# PowerAmplifier_Control.net
KiCad netlist of a schematic drawn in Altium Designer
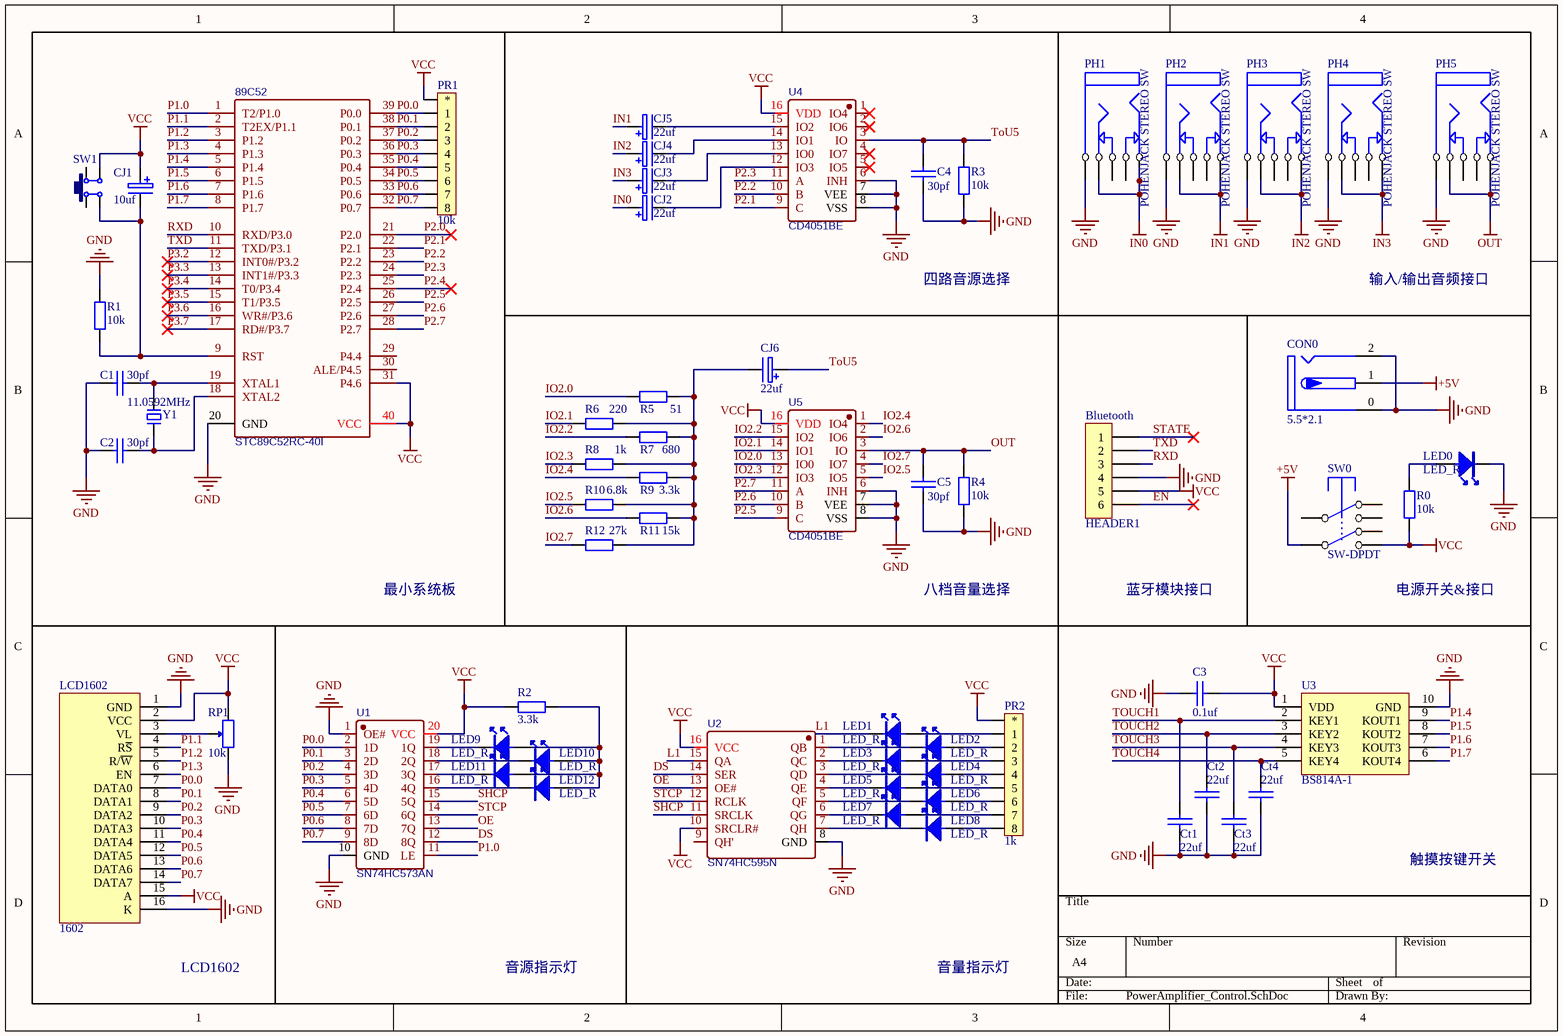
[diagram p0: PowerAmplifier_Control.SchDoc]

(export (version "E")
  (design (tool "Eeschema 10.0.6"))
  (components
    (comp (ref "89C52")
      (value "STC89C52RC-40I")
      (footprint "DIP-40_LS15.24-L52.58-W13.97-PITCH2.54")
      (fields (field (name "BOM_SUPPLIER PART") "C14022"))
      (libsource (lib "电子时钟元件库") (part "STC89C52RC-40I"))
    )
    (comp (ref "Bluetooth")
      (value "HEADER1")
      (footprint "sip-6")
      (description "Connector")
      (libsource (lib "基地库3.0mini") (part "CON6"))
    )
    (comp (ref "C1") (value "30pf") (footprint "CAP2") (libsource (lib "基地库3.0mini") (part "CAP1")))
    (comp (ref "C2") (value "30pf") (footprint "CAP2") (libsource (lib "基地库3.0mini") (part "CAP1")))
    (comp (ref "C3") (value "0.1uf") (footprint "CAP2") (libsource (lib "基地库3.0mini") (part "CAP1")))
    (comp (ref "C4") (value "30pf") (footprint "CAP2") (libsource (lib "基地库3.0mini") (part "CAP1")))
    (comp (ref "C5") (value "30pf") (footprint "CAP2") (libsource (lib "基地库3.0mini") (part "CAP1")))
    (comp (ref "CJ1") (value "10uf") (footprint "CAO1") (libsource (lib "基地库3.0mini") (part "CAP3")))
    (comp (ref "CJ2") (value "22uf") (footprint "CAO1") (libsource (lib "基地库3.0mini") (part "CAP3")))
    (comp (ref "CJ3") (value "22uf") (footprint "CAO1") (libsource (lib "基地库3.0mini") (part "CAP3")))
    (comp (ref "CJ4") (value "22uf") (footprint "CAO1") (libsource (lib "基地库3.0mini") (part "CAP3")))
    (comp (ref "CJ5") (value "22uf") (footprint "CAO1") (libsource (lib "基地库3.0mini") (part "CAP3")))
    (comp (ref "CJ6") (value "22uf") (footprint "CAO1") (libsource (lib "基地库3.0mini") (part "CAP3")))
    (comp (ref "CON0")
      (value "5.5*2.1")
      (footprint "DC-005P")
      (description "带屏蔽DC电源接口")
      (fields (field (name "版权归属") "源创客"))
      (libsource (lib "7-电源接口") (part "DC-005P"))
    )
    (comp (ref "Ct1") (value "22uf") (footprint "CAP2") (libsource (lib "基地库3.0mini") (part "CAP1")))
    (comp (ref "Ct2") (value "22uf") (footprint "CAP2") (libsource (lib "基地库3.0mini") (part "CAP1")))
    (comp (ref "Ct3") (value "22uf") (footprint "CAP2") (libsource (lib "基地库3.0mini") (part "CAP1")))
    (comp (ref "Ct4") (value "22uf") (footprint "CAP2") (libsource (lib "基地库3.0mini") (part "CAP1")))
    (comp (ref "LCD1602") (value "1602") (footprint "1602") (libsource (lib "基地库3.0mini") (part "1602")))
    (comp (ref "LED0") (value "LED_R") (footprint "LED_1206") (libsource (lib "基地库3.0mini") (part "LED")))
    (comp (ref "LED1") (value "LED_R") (footprint "LED_1206") (libsource (lib "基地库3.0mini") (part "LED")))
    (comp (ref "LED2") (value "LED_R") (footprint "LED_1206") (libsource (lib "基地库3.0mini") (part "LED")))
    (comp (ref "LED3") (value "LED_R") (footprint "LED_1206") (libsource (lib "基地库3.0mini") (part "LED")))
    (comp (ref "LED4") (value "LED_R") (footprint "LED_1206") (libsource (lib "基地库3.0mini") (part "LED")))
    (comp (ref "LED5") (value "LED_R") (footprint "LED_1206") (libsource (lib "基地库3.0mini") (part "LED")))
    (comp (ref "LED6") (value "LED_R") (footprint "LED_1206") (libsource (lib "基地库3.0mini") (part "LED")))
    (comp (ref "LED7") (value "LED_R") (footprint "LED_1206") (libsource (lib "基地库3.0mini") (part "LED")))
    (comp (ref "LED8") (value "LED_R") (footprint "LED_1206") (libsource (lib "基地库3.0mini") (part "LED")))
    (comp (ref "LED9") (value "LED_R") (footprint "LED_1206") (libsource (lib "基地库3.0mini") (part "LED")))
    (comp (ref "LED10") (value "LED_R") (footprint "LED_1206") (libsource (lib "基地库3.0mini") (part "LED")))
    (comp (ref "LED11") (value "LED_R") (footprint "LED_1206") (libsource (lib "基地库3.0mini") (part "LED")))
    (comp (ref "LED12") (value "LED_R") (footprint "LED_1206") (libsource (lib "基地库3.0mini") (part "LED")))
    (comp (ref "PH1")
      (value "POHENJACK STEREO SW")
      (footprint "POHENJACK STEREO SW")
      (libsource (lib "电子电路集成库") (part "POHENJACK STEREO SW"))
    )
    (comp (ref "PH2")
      (value "POHENJACK STEREO SW")
      (footprint "POHENJACK STEREO SW")
      (libsource (lib "电子电路集成库") (part "POHENJACK STEREO SW"))
    )
    (comp (ref "PH3")
      (value "POHENJACK STEREO SW")
      (footprint "POHENJACK STEREO SW")
      (libsource (lib "电子电路集成库") (part "POHENJACK STEREO SW"))
    )
    (comp (ref "PH4")
      (value "POHENJACK STEREO SW")
      (footprint "POHENJACK STEREO SW")
      (libsource (lib "电子电路集成库") (part "POHENJACK STEREO SW"))
    )
    (comp (ref "PH5")
      (value "POHENJACK STEREO SW")
      (footprint "POHENJACK STEREO SW")
      (libsource (lib "电子电路集成库") (part "POHENJACK STEREO SW"))
    )
    (comp (ref "PR1") (value "10k") (footprint "RP1") (libsource (lib "基地库3.0mini") (part "PRES1")))
    (comp (ref "PR2") (value "1k") (footprint "RP1") (libsource (lib "基地库3.0mini") (part "PRES1")))
    (comp (ref "R0")
      (value "10k")
      (footprint "AXIAL0.4")
      (description "贴片电阻")
      (fields (field (name "版权归属") "源创客"))
      (libsource (lib "9-电阻-电容-电感") (part "R"))
    )
    (comp (ref "R1")
      (value "10k")
      (footprint "AXIAL0.4")
      (description "贴片电阻")
      (fields (field (name "版权归属") "源创客"))
      (libsource (lib "9-电阻-电容-电感") (part "R"))
    )
    (comp (ref "R2")
      (value "3.3k")
      (footprint "AXIAL0.4")
      (description "贴片电阻")
      (fields (field (name "版权归属") "源创客"))
      (libsource (lib "9-电阻-电容-电感") (part "R"))
    )
    (comp (ref "R3")
      (value "10k")
      (footprint "AXIAL0.4")
      (description "贴片电阻")
      (fields (field (name "版权归属") "源创客"))
      (libsource (lib "9-电阻-电容-电感") (part "R"))
    )
    (comp (ref "R4")
      (value "10k")
      (footprint "AXIAL0.4")
      (description "贴片电阻")
      (fields (field (name "版权归属") "源创客"))
      (libsource (lib "9-电阻-电容-电感") (part "R"))
    )
    (comp (ref "R5")
      (value "51")
      (footprint "AXIAL0.4")
      (description "贴片电阻")
      (fields (field (name "版权归属") "源创客"))
      (libsource (lib "9-电阻-电容-电感") (part "R"))
    )
    (comp (ref "R6")
      (value "220")
      (footprint "AXIAL0.4")
      (description "贴片电阻")
      (fields (field (name "版权归属") "源创客"))
      (libsource (lib "9-电阻-电容-电感") (part "R"))
    )
    (comp (ref "R7")
      (value "680")
      (footprint "AXIAL0.4")
      (description "贴片电阻")
      (fields (field (name "版权归属") "源创客"))
      (libsource (lib "9-电阻-电容-电感") (part "R"))
    )
    (comp (ref "R8")
      (value "1k")
      (footprint "AXIAL0.4")
      (description "贴片电阻")
      (fields (field (name "版权归属") "源创客"))
      (libsource (lib "9-电阻-电容-电感") (part "R"))
    )
    (comp (ref "R9")
      (value "3.3k")
      (footprint "AXIAL0.4")
      (description "贴片电阻")
      (fields (field (name "版权归属") "源创客"))
      (libsource (lib "9-电阻-电容-电感") (part "R"))
    )
    (comp (ref "R10")
      (value "6.8k")
      (footprint "AXIAL0.4")
      (description "贴片电阻")
      (fields (field (name "版权归属") "源创客"))
      (libsource (lib "9-电阻-电容-电感") (part "R"))
    )
    (comp (ref "R11")
      (value "15k")
      (footprint "AXIAL0.4")
      (description "贴片电阻")
      (fields (field (name "版权归属") "源创客"))
      (libsource (lib "9-电阻-电容-电感") (part "R"))
    )
    (comp (ref "R12")
      (value "27k")
      (footprint "AXIAL0.4")
      (description "贴片电阻")
      (fields (field (name "版权归属") "源创客"))
      (libsource (lib "9-电阻-电容-电感") (part "R"))
    )
    (comp (ref "RP1")
      (value "10k")
      (footprint "3296W")
      (description "插件单联电位器")
      (fields (field (name "版权归属") "源创客"))
      (libsource (lib "9-电阻-电容-电感") (part "RP-ID"))
    )
    (comp (ref "SW0") (value "SW-DPDT") (footprint "SWH7*7") (libsource (lib "基地库3.0mini") (part "SW-DPDT")))
    (comp (ref "SW1")
      (value "6x6x5")
      (footprint "TSW DIP-6*6*6")
      (description "直插6x6轻触开关")
      (fields (field (name "版权归属") "源创客"))
      (libsource (lib "5-按键-开关") (part "TSW DIP-6x6"))
    )
    (comp (ref "U1")
      (value "SN74HC573AN")
      (footprint "DIP-20_L26.8-W6.4-P2.54-LS7.6-BL")
      (fields (field (name "BOM_SUPPLIER PART") "C5196"))
      (libsource (lib "74HC573AN") (part "SN74HC573AN"))
    )
    (comp (ref "U2")
      (value "SN74HC595N")
      (footprint "DIP-16_L19.8-W6.5-P2.54-LS7.6-BL")
      (fields (field (name "BOM_SUPPLIER PART") "C78711"))
      (libsource (lib "74HC595N") (part "SN74HC595N"))
    )
    (comp (ref "U3")
      (value "BS814A-1")
      (footprint "MSOP10_N")
      (description "4键电容触摸按键芯片")
      (fields (field (name "版权归属") "源创客"))
      (libsource (lib "14-IC芯片") (part "BS814A"))
    )
    (comp (ref "U4")
      (value "CD4051BE")
      (footprint "DIP-16_L20.0-W6.4-P2.54-LS7.6-BL")
      (fields (field (name "BOM_SUPPLIER PART") "C5200"))
      (libsource (lib "CD4051BE") (part "CD4051BE"))
    )
    (comp (ref "U5")
      (value "CD4051BE")
      (footprint "DIP-16_L20.0-W6.4-P2.54-LS7.6-BL")
      (fields (field (name "BOM_SUPPLIER PART") "C5200"))
      (libsource (lib "CD4051BE") (part "CD4051BE"))
    )
    (comp (ref "Y1")
      (value "11.0592MHz")
      (footprint "OSC HC-49S")
      (description "2脚无源脚晶振")
      (fields (field (name "版权归属") "源创客"))
      (libsource (lib "6-保险丝-晶振") (part "XTAL-2P"))
    )
  )
  (nets
    (net (code "1") (name "+5V") (class "Default")
      (node (ref "CON0") (pin "1") (pintype "power_in"))
      (node (ref "SW0") (pin "5") (pinfunction "5_5") (pintype "passive"))
    )
    (net (code "2") (name "/DS") (class "Default")
      (node (ref "U1") (pin "12") (pinfunction "8Q_12") (pintype "passive"))
      (node (ref "U2") (pin "14") (pinfunction "SER_14") (pintype "passive"))
    )
    (net (code "3") (name "/EN") (class "Default")
      (node (ref "Bluetooth") (pin "6") (pinfunction "6_6") (pintype "passive+no_connect"))
    )
    (net (code "4") (name "/IO2.0") (class "Default")
      (node (ref "R5") (pin "1") (pinfunction "1_1") (pintype "passive"))
      (node (ref "U5") (pin "13") (pinfunction "IO0_13") (pintype "passive"))
    )
    (net (code "5") (name "/IO2.1") (class "Default")
      (node (ref "R6") (pin "1") (pinfunction "1_1") (pintype "passive"))
      (node (ref "U5") (pin "14") (pinfunction "IO1_14") (pintype "passive"))
    )
    (net (code "6") (name "/IO2.2") (class "Default")
      (node (ref "R7") (pin "1") (pinfunction "1_1") (pintype "passive"))
      (node (ref "U5") (pin "15") (pinfunction "IO2_15") (pintype "passive"))
    )
    (net (code "7") (name "/IO2.3") (class "Default")
      (node (ref "R8") (pin "1") (pinfunction "1_1") (pintype "passive"))
      (node (ref "U5") (pin "12") (pinfunction "IO3_12") (pintype "passive"))
    )
    (net (code "8") (name "/IO2.4") (class "Default")
      (node (ref "R9") (pin "1") (pinfunction "1_1") (pintype "passive"))
      (node (ref "U5") (pin "1") (pinfunction "IO4_1") (pintype "passive"))
    )
    (net (code "9") (name "/IO2.5") (class "Default")
      (node (ref "R10") (pin "1") (pinfunction "1_1") (pintype "passive"))
      (node (ref "U5") (pin "5") (pinfunction "IO5_5") (pintype "passive"))
    )
    (net (code "10") (name "/IO2.6") (class "Default")
      (node (ref "R11") (pin "1") (pinfunction "1_1") (pintype "passive"))
      (node (ref "U5") (pin "2") (pinfunction "IO6_2") (pintype "passive"))
    )
    (net (code "11") (name "/IO2.7") (class "Default")
      (node (ref "R12") (pin "1") (pinfunction "1_1") (pintype "passive"))
      (node (ref "U5") (pin "4") (pinfunction "IO7_4") (pintype "passive"))
    )
    (net (code "12") (name "/L1") (class "Default")
      (node (ref "LED1") (pin "2") (pinfunction "2_2") (pintype "passive"))
      (node (ref "U2") (pin "15") (pinfunction "QA_15") (pintype "passive"))
    )
    (net (code "13") (name "/OE") (class "Default")
      (node (ref "U1") (pin "13") (pinfunction "7Q_13") (pintype "passive"))
      (node (ref "U2") (pin "13") (pinfunction "OE#_13") (pintype "passive"))
    )
    (net (code "14") (name "/P0.0") (class "Default")
      (node (ref "89C52") (pin "39") (pinfunction "P0.0_39") (pintype "passive"))
      (node (ref "LCD1602") (pin "7") (pinfunction "DATA0_7") (pintype "passive"))
      (node (ref "PR1") (pin "2") (pinfunction "1_2") (pintype "passive"))
      (node (ref "U1") (pin "2") (pinfunction "1D_2") (pintype "passive"))
    )
    (net (code "15") (name "/P0.1") (class "Default")
      (node (ref "89C52") (pin "38") (pinfunction "P0.1_38") (pintype "passive"))
      (node (ref "LCD1602") (pin "8") (pinfunction "DATA1_8") (pintype "passive"))
      (node (ref "PR1") (pin "3") (pinfunction "2_3") (pintype "passive"))
      (node (ref "U1") (pin "3") (pinfunction "2D_3") (pintype "passive"))
    )
    (net (code "16") (name "/P0.2") (class "Default")
      (node (ref "89C52") (pin "37") (pinfunction "P0.2_37") (pintype "passive"))
      (node (ref "LCD1602") (pin "9") (pinfunction "DATA2_9") (pintype "passive"))
      (node (ref "PR1") (pin "4") (pinfunction "3_4") (pintype "passive"))
      (node (ref "U1") (pin "4") (pinfunction "3D_4") (pintype "passive"))
    )
    (net (code "17") (name "/P0.3") (class "Default")
      (node (ref "89C52") (pin "36") (pinfunction "P0.3_36") (pintype "passive"))
      (node (ref "LCD1602") (pin "10") (pinfunction "DATA3_10") (pintype "passive"))
      (node (ref "PR1") (pin "5") (pinfunction "4_5") (pintype "passive"))
      (node (ref "U1") (pin "5") (pinfunction "4D_5") (pintype "passive"))
    )
    (net (code "18") (name "/P0.4") (class "Default")
      (node (ref "89C52") (pin "35") (pinfunction "P0.4_35") (pintype "passive"))
      (node (ref "LCD1602") (pin "11") (pinfunction "DATA4_11") (pintype "passive"))
      (node (ref "PR1") (pin "6") (pinfunction "5_6") (pintype "passive"))
      (node (ref "U1") (pin "6") (pinfunction "5D_6") (pintype "passive"))
    )
    (net (code "19") (name "/P0.5") (class "Default")
      (node (ref "89C52") (pin "34") (pinfunction "P0.5_34") (pintype "passive"))
      (node (ref "LCD1602") (pin "12") (pinfunction "DATA5_12") (pintype "passive"))
      (node (ref "PR1") (pin "7") (pinfunction "6_7") (pintype "passive"))
      (node (ref "U1") (pin "7") (pinfunction "6D_7") (pintype "passive"))
    )
    (net (code "20") (name "/P0.6") (class "Default")
      (node (ref "89C52") (pin "33") (pinfunction "P0.6_33") (pintype "passive"))
      (node (ref "LCD1602") (pin "13") (pinfunction "DATA6_13") (pintype "passive"))
      (node (ref "PR1") (pin "8") (pinfunction "7_8") (pintype "passive"))
      (node (ref "U1") (pin "8") (pinfunction "7D_8") (pintype "passive"))
    )
    (net (code "21") (name "/P0.7") (class "Default")
      (node (ref "89C52") (pin "32") (pinfunction "P0.7_32") (pintype "passive"))
      (node (ref "LCD1602") (pin "14") (pinfunction "DATA7_14") (pintype "passive"))
      (node (ref "PR1") (pin "9") (pinfunction "8_9") (pintype "passive"))
      (node (ref "U1") (pin "9") (pinfunction "8D_9") (pintype "passive"))
    )
    (net (code "22") (name "/P1.0") (class "Default")
      (node (ref "89C52") (pin "1") (pinfunction "T2/P1.0_1") (pintype "passive"))
      (node (ref "U1") (pin "11") (pinfunction "LE_11") (pintype "passive"))
    )
    (net (code "23") (name "/P1.1") (class "Default")
      (node (ref "89C52") (pin "2") (pinfunction "T2EX/P1.1_2") (pintype "passive"))
      (node (ref "LCD1602") (pin "4") (pinfunction "R~{S}_4") (pintype "passive"))
    )
    (net (code "24") (name "/P1.2") (class "Default")
      (node (ref "89C52") (pin "3") (pinfunction "P1.2_3") (pintype "passive"))
      (node (ref "LCD1602") (pin "5") (pinfunction "R/~{W}_5") (pintype "passive"))
    )
    (net (code "25") (name "/P1.3") (class "Default")
      (node (ref "89C52") (pin "4") (pinfunction "P1.3_4") (pintype "passive"))
      (node (ref "LCD1602") (pin "6") (pinfunction "EN_6") (pintype "passive"))
    )
    (net (code "26") (name "/P1.4") (class "Default")
      (node (ref "89C52") (pin "5") (pinfunction "P1.4_5") (pintype "passive"))
      (node (ref "U3") (pin "9") (pinfunction "KOUT1_9") (pintype "passive"))
    )
    (net (code "27") (name "/P1.5") (class "Default")
      (node (ref "89C52") (pin "6") (pinfunction "P1.5_6") (pintype "passive"))
      (node (ref "U3") (pin "8") (pinfunction "KOUT2_8") (pintype "passive"))
    )
    (net (code "28") (name "/P1.6") (class "Default")
      (node (ref "89C52") (pin "7") (pinfunction "P1.6_7") (pintype "passive"))
      (node (ref "U3") (pin "7") (pinfunction "KOUT3_7") (pintype "passive"))
    )
    (net (code "29") (name "/P1.7") (class "Default")
      (node (ref "89C52") (pin "8") (pinfunction "P1.7_8") (pintype "passive"))
      (node (ref "U3") (pin "6") (pinfunction "KOUT4_6") (pintype "passive"))
    )
    (net (code "30") (name "/P2.0") (class "Default")
      (node (ref "89C52") (pin "21") (pinfunction "P2.0_21") (pintype "passive+no_connect"))
    )
    (net (code "31") (name "/P2.1") (class "Default")
      (node (ref "89C52") (pin "22") (pinfunction "P2.1_22") (pintype "passive"))
      (node (ref "U4") (pin "9") (pinfunction "C_9") (pintype "passive"))
    )
    (net (code "32") (name "/P2.2") (class "Default")
      (node (ref "89C52") (pin "23") (pinfunction "P2.2_23") (pintype "passive"))
      (node (ref "U4") (pin "10") (pinfunction "B_10") (pintype "passive"))
    )
    (net (code "33") (name "/P2.3") (class "Default")
      (node (ref "89C52") (pin "24") (pinfunction "P2.3_24") (pintype "passive"))
      (node (ref "U4") (pin "11") (pinfunction "A_11") (pintype "passive"))
    )
    (net (code "34") (name "/P2.4") (class "Default")
      (node (ref "89C52") (pin "25") (pinfunction "P2.4_25") (pintype "passive+no_connect"))
    )
    (net (code "35") (name "/P2.5") (class "Default")
      (node (ref "89C52") (pin "26") (pinfunction "P2.5_26") (pintype "passive"))
      (node (ref "U5") (pin "9") (pinfunction "C_9") (pintype "passive"))
    )
    (net (code "36") (name "/P2.6") (class "Default")
      (node (ref "89C52") (pin "27") (pinfunction "P2.6_27") (pintype "passive"))
      (node (ref "U5") (pin "10") (pinfunction "B_10") (pintype "passive"))
    )
    (net (code "37") (name "/P2.7") (class "Default")
      (node (ref "89C52") (pin "28") (pinfunction "P2.7_28") (pintype "passive"))
      (node (ref "U5") (pin "11") (pinfunction "A_11") (pintype "passive"))
    )
    (net (code "38") (name "/P3.2") (class "Default")
      (node (ref "89C52") (pin "12") (pinfunction "INT0#/P3.2_12") (pintype "passive+no_connect"))
    )
    (net (code "39") (name "/P3.3") (class "Default")
      (node (ref "89C52") (pin "13") (pinfunction "INT1#/P3.3_13") (pintype "passive+no_connect"))
    )
    (net (code "40") (name "/P3.4") (class "Default")
      (node (ref "89C52") (pin "14") (pinfunction "T0/P3.4_14") (pintype "passive+no_connect"))
    )
    (net (code "41") (name "/P3.5") (class "Default")
      (node (ref "89C52") (pin "15") (pinfunction "T1/P3.5_15") (pintype "passive+no_connect"))
    )
    (net (code "42") (name "/P3.6") (class "Default")
      (node (ref "89C52") (pin "16") (pinfunction "WR#/P3.6_16") (pintype "passive+no_connect"))
    )
    (net (code "43") (name "/P3.7") (class "Default")
      (node (ref "89C52") (pin "17") (pinfunction "RD#/P3.7_17") (pintype "passive+no_connect"))
    )
    (net (code "44") (name "/RXD") (class "Default")
      (node (ref "89C52") (pin "10") (pinfunction "RXD/P3.0_10") (pintype "passive"))
      (node (ref "Bluetooth") (pin "3") (pinfunction "3_3") (pintype "passive"))
    )
    (net (code "45") (name "/SHCP") (class "Default")
      (node (ref "U1") (pin "15") (pinfunction "5Q_15") (pintype "passive"))
      (node (ref "U2") (pin "11") (pinfunction "SRCLK_11") (pintype "passive"))
    )
    (net (code "46") (name "/STATE") (class "Default")
      (node (ref "Bluetooth") (pin "1") (pinfunction "1_1") (pintype "passive+no_connect"))
    )
    (net (code "47") (name "/STCP") (class "Default")
      (node (ref "U1") (pin "14") (pinfunction "6Q_14") (pintype "passive"))
      (node (ref "U2") (pin "12") (pinfunction "RCLK_12") (pintype "passive"))
    )
    (net (code "48") (name "/TOUCH1") (class "Default")
      (node (ref "Ct1") (pin "1") (pinfunction "1_1") (pintype "passive"))
      (node (ref "U3") (pin "2") (pinfunction "KEY1_2") (pintype "passive"))
    )
    (net (code "49") (name "/TOUCH2") (class "Default")
      (node (ref "Ct2") (pin "1") (pinfunction "1_1") (pintype "passive"))
      (node (ref "U3") (pin "3") (pinfunction "KEY2_3") (pintype "passive"))
    )
    (net (code "50") (name "/TOUCH3") (class "Default")
      (node (ref "Ct3") (pin "1") (pinfunction "1_1") (pintype "passive"))
      (node (ref "U3") (pin "4") (pinfunction "KEY3_4") (pintype "passive"))
    )
    (net (code "51") (name "/TOUCH4") (class "Default")
      (node (ref "Ct4") (pin "1") (pinfunction "1_1") (pintype "passive"))
      (node (ref "U3") (pin "5") (pinfunction "KEY4_5") (pintype "passive"))
    )
    (net (code "52") (name "/TXD") (class "Default")
      (node (ref "89C52") (pin "11") (pinfunction "TXD/P3.1_11") (pintype "passive"))
      (node (ref "Bluetooth") (pin "2") (pinfunction "2_2") (pintype "passive"))
    )
    (net (code "53") (name "/ToU5") (class "Default")
      (node (ref "C4") (pin "1") (pinfunction "1_1") (pintype "passive"))
      (node (ref "CJ6") (pin "1") (pintype "passive"))
      (node (ref "R3") (pin "2") (pinfunction "2_2") (pintype "passive"))
      (node (ref "U4") (pin "3") (pinfunction "IO_3") (pintype "passive"))
    )
    (net (code "54") (name "GND") (class "Default")
      (node (ref "89C52") (pin "20") (pinfunction "GND_20") (pintype "passive"))
      (node (ref "Bluetooth") (pin "4") (pinfunction "4_4") (pintype "passive"))
      (node (ref "C1") (pin "2") (pinfunction "2_2") (pintype "passive"))
      (node (ref "C2") (pin "2") (pinfunction "2_2") (pintype "passive"))
      (node (ref "C3") (pin "1") (pinfunction "1_1") (pintype "passive"))
      (node (ref "C4") (pin "2") (pinfunction "2_2") (pintype "passive"))
      (node (ref "C5") (pin "2") (pinfunction "2_2") (pintype "passive"))
      (node (ref "CON0") (pin "0") (pintype "power_in"))
      (node (ref "CON0") (pin "2") (pintype "power_in"))
      (node (ref "Ct1") (pin "2") (pinfunction "2_2") (pintype "passive"))
      (node (ref "Ct2") (pin "2") (pinfunction "2_2") (pintype "passive"))
      (node (ref "Ct3") (pin "2") (pinfunction "2_2") (pintype "passive"))
      (node (ref "Ct4") (pin "2") (pinfunction "2_2") (pintype "passive"))
      (node (ref "LCD1602") (pin "1") (pinfunction "GND_1") (pintype "passive"))
      (node (ref "LCD1602") (pin "16") (pinfunction "K_16") (pintype "passive"))
      (node (ref "LED0") (pin "2") (pinfunction "2_2") (pintype "passive"))
      (node (ref "PH1") (pin "5") (pinfunction "E_5") (pintype "passive"))
      (node (ref "PH2") (pin "5") (pinfunction "E_5") (pintype "passive"))
      (node (ref "PH3") (pin "5") (pinfunction "E_5") (pintype "passive"))
      (node (ref "PH4") (pin "5") (pinfunction "E_5") (pintype "passive"))
      (node (ref "PH5") (pin "5") (pinfunction "E_5") (pintype "passive"))
      (node (ref "R1") (pin "1") (pinfunction "1_1") (pintype "passive"))
      (node (ref "R3") (pin "1") (pinfunction "1_1") (pintype "passive"))
      (node (ref "R4") (pin "1") (pinfunction "1_1") (pintype "passive"))
      (node (ref "RP1") (pin "1") (pinfunction "1_1") (pintype "passive"))
      (node (ref "U1") (pin "1") (pinfunction "OE#_1") (pintype "passive"))
      (node (ref "U1") (pin "10") (pinfunction "GND_10") (pintype "passive"))
      (node (ref "U2") (pin "8") (pinfunction "GND_8") (pintype "passive"))
      (node (ref "U3") (pin "10") (pinfunction "GND_10") (pintype "passive"))
      (node (ref "U4") (pin "6") (pinfunction "INH_6") (pintype "passive"))
      (node (ref "U4") (pin "7") (pinfunction "VEE_7") (pintype "passive"))
      (node (ref "U4") (pin "8") (pinfunction "VSS_8") (pintype "passive"))
      (node (ref "U5") (pin "6") (pinfunction "INH_6") (pintype "passive"))
      (node (ref "U5") (pin "7") (pinfunction "VEE_7") (pintype "passive"))
      (node (ref "U5") (pin "8") (pinfunction "VSS_8") (pintype "passive"))
    )
    (net (code "55") (name "IN0") (class "Default")
      (node (ref "CJ2") (pin "1") (pintype "passive"))
      (node (ref "PH1") (pin "1") (pinfunction "A_1") (pintype "passive"))
      (node (ref "PH1") (pin "4") (pinfunction "D_4") (pintype "passive"))
    )
    (net (code "56") (name "IN1") (class "Default")
      (node (ref "CJ5") (pin "1") (pintype "passive"))
      (node (ref "PH2") (pin "1") (pinfunction "A_1") (pintype "passive"))
      (node (ref "PH2") (pin "4") (pinfunction "D_4") (pintype "passive"))
    )
    (net (code "57") (name "IN2") (class "Default")
      (node (ref "CJ4") (pin "1") (pintype "passive"))
      (node (ref "PH3") (pin "1") (pinfunction "A_1") (pintype "passive"))
      (node (ref "PH3") (pin "4") (pinfunction "D_4") (pintype "passive"))
    )
    (net (code "58") (name "IN3") (class "Default")
      (node (ref "CJ3") (pin "1") (pintype "passive"))
      (node (ref "PH4") (pin "1") (pinfunction "A_1") (pintype "passive"))
      (node (ref "PH4") (pin "4") (pinfunction "D_4") (pintype "passive"))
    )
    (net (code "59") (name "Net-(89C52-RST)") (class "Default")
      (node (ref "89C52") (pin "9") (pinfunction "RST_9") (pintype "passive"))
      (node (ref "CJ1") (pin "2") (pintype "passive"))
      (node (ref "R1") (pin "2") (pinfunction "2_2") (pintype "passive"))
      (node (ref "SW1") (pin "4") (pinfunction "4_4") (pintype "passive"))
    )
    (net (code "60") (name "Net-(89C52-XTAL1)") (class "Default")
      (node (ref "89C52") (pin "19") (pinfunction "XTAL1_19") (pintype "passive"))
      (node (ref "C1") (pin "1") (pinfunction "1_1") (pintype "passive"))
      (node (ref "Y1") (pin "2") (pinfunction "2_2") (pintype "passive"))
    )
    (net (code "61") (name "Net-(89C52-XTAL2)") (class "Default")
      (node (ref "89C52") (pin "18") (pinfunction "XTAL2_18") (pintype "passive"))
      (node (ref "C2") (pin "1") (pinfunction "1_1") (pintype "passive"))
      (node (ref "Y1") (pin "1") (pinfunction "1_1") (pintype "passive"))
    )
    (net (code "62") (name "Net-(CJ6-Pad2)") (class "Default")
      (node (ref "CJ6") (pin "2") (pintype "passive"))
      (node (ref "R10") (pin "2") (pinfunction "2_2") (pintype "passive"))
      (node (ref "R11") (pin "2") (pinfunction "2_2") (pintype "passive"))
      (node (ref "R12") (pin "2") (pinfunction "2_2") (pintype "passive"))
      (node (ref "R5") (pin "2") (pinfunction "2_2") (pintype "passive"))
      (node (ref "R6") (pin "2") (pinfunction "2_2") (pintype "passive"))
      (node (ref "R7") (pin "2") (pinfunction "2_2") (pintype "passive"))
      (node (ref "R8") (pin "2") (pinfunction "2_2") (pintype "passive"))
      (node (ref "R9") (pin "2") (pinfunction "2_2") (pintype "passive"))
    )
    (net (code "63") (name "Net-(LCD1602-VL)") (class "Default")
      (node (ref "LCD1602") (pin "3") (pinfunction "VL_3") (pintype "passive"))
      (node (ref "RP1") (pin "2") (pinfunction "2_2") (pintype "passive"))
    )
    (net (code "64") (name "Net-(LED0-Pad1)") (class "Default")
      (node (ref "LED0") (pin "1") (pinfunction "1_1") (pintype "passive"))
      (node (ref "R0") (pin "1") (pinfunction "1_1") (pintype "passive"))
    )
    (net (code "65") (name "Net-(LED10-Pad1)") (class "Default")
      (node (ref "LED10") (pin "1") (pinfunction "1_1") (pintype "passive"))
      (node (ref "LED11") (pin "1") (pinfunction "1_1") (pintype "passive"))
      (node (ref "LED12") (pin "1") (pinfunction "1_1") (pintype "passive"))
      (node (ref "LED9") (pin "1") (pinfunction "1_1") (pintype "passive"))
      (node (ref "R2") (pin "1") (pinfunction "1_1") (pintype "passive"))
    )
    (net (code "66") (name "Net-(PR2-1)") (class "Default")
      (node (ref "LED1") (pin "1") (pinfunction "1_1") (pintype "passive"))
      (node (ref "PR2") (pin "2") (pinfunction "1_2") (pintype "passive"))
    )
    (net (code "67") (name "Net-(PR2-2)") (class "Default")
      (node (ref "LED2") (pin "1") (pinfunction "1_1") (pintype "passive"))
      (node (ref "PR2") (pin "3") (pinfunction "2_3") (pintype "passive"))
    )
    (net (code "68") (name "Net-(PR2-3)") (class "Default")
      (node (ref "LED3") (pin "1") (pinfunction "1_1") (pintype "passive"))
      (node (ref "PR2") (pin "4") (pinfunction "3_4") (pintype "passive"))
    )
    (net (code "69") (name "Net-(PR2-4)") (class "Default")
      (node (ref "LED4") (pin "1") (pinfunction "1_1") (pintype "passive"))
      (node (ref "PR2") (pin "5") (pinfunction "4_5") (pintype "passive"))
    )
    (net (code "70") (name "Net-(PR2-5)") (class "Default")
      (node (ref "LED5") (pin "1") (pinfunction "1_1") (pintype "passive"))
      (node (ref "PR2") (pin "6") (pinfunction "5_6") (pintype "passive"))
    )
    (net (code "71") (name "Net-(PR2-6)") (class "Default")
      (node (ref "LED6") (pin "1") (pinfunction "1_1") (pintype "passive"))
      (node (ref "PR2") (pin "7") (pinfunction "6_7") (pintype "passive"))
    )
    (net (code "72") (name "Net-(PR2-7)") (class "Default")
      (node (ref "LED7") (pin "1") (pinfunction "1_1") (pintype "passive"))
      (node (ref "PR2") (pin "8") (pinfunction "7_8") (pintype "passive"))
    )
    (net (code "73") (name "Net-(PR2-8)") (class "Default")
      (node (ref "LED8") (pin "1") (pinfunction "1_1") (pintype "passive"))
      (node (ref "PR2") (pin "9") (pinfunction "8_9") (pintype "passive"))
    )
    (net (code "74") (name "Net-(U1-1Q)") (class "Default")
      (node (ref "LED9") (pin "2") (pinfunction "2_2") (pintype "passive"))
      (node (ref "U1") (pin "19") (pinfunction "1Q_19") (pintype "passive"))
    )
    (net (code "75") (name "Net-(U1-2Q)") (class "Default")
      (node (ref "LED10") (pin "2") (pinfunction "2_2") (pintype "passive"))
      (node (ref "U1") (pin "18") (pinfunction "2Q_18") (pintype "passive"))
    )
    (net (code "76") (name "Net-(U1-3Q)") (class "Default")
      (node (ref "LED11") (pin "2") (pinfunction "2_2") (pintype "passive"))
      (node (ref "U1") (pin "17") (pinfunction "3Q_17") (pintype "passive"))
    )
    (net (code "77") (name "Net-(U1-4Q)") (class "Default")
      (node (ref "LED12") (pin "2") (pinfunction "2_2") (pintype "passive"))
      (node (ref "U1") (pin "16") (pinfunction "4Q_16") (pintype "passive"))
    )
    (net (code "78") (name "Net-(U2-QB)") (class "Default")
      (node (ref "LED2") (pin "2") (pinfunction "2_2") (pintype "passive"))
      (node (ref "U2") (pin "1") (pinfunction "QB_1") (pintype "passive"))
    )
    (net (code "79") (name "Net-(U2-QC)") (class "Default")
      (node (ref "LED3") (pin "2") (pinfunction "2_2") (pintype "passive"))
      (node (ref "U2") (pin "2") (pinfunction "QC_2") (pintype "passive"))
    )
    (net (code "80") (name "Net-(U2-QD)") (class "Default")
      (node (ref "LED4") (pin "2") (pinfunction "2_2") (pintype "passive"))
      (node (ref "U2") (pin "3") (pinfunction "QD_3") (pintype "passive"))
    )
    (net (code "81") (name "Net-(U2-QE)") (class "Default")
      (node (ref "LED5") (pin "2") (pinfunction "2_2") (pintype "passive"))
      (node (ref "U2") (pin "4") (pinfunction "QE_4") (pintype "passive"))
    )
    (net (code "82") (name "Net-(U2-QF)") (class "Default")
      (node (ref "LED6") (pin "2") (pinfunction "2_2") (pintype "passive"))
      (node (ref "U2") (pin "5") (pinfunction "QF_5") (pintype "passive"))
    )
    (net (code "83") (name "Net-(U2-QG)") (class "Default")
      (node (ref "LED7") (pin "2") (pinfunction "2_2") (pintype "passive"))
      (node (ref "U2") (pin "6") (pinfunction "QG_6") (pintype "passive"))
    )
    (net (code "84") (name "Net-(U2-QH)") (class "Default")
      (node (ref "LED8") (pin "2") (pinfunction "2_2") (pintype "passive"))
      (node (ref "U2") (pin "7") (pinfunction "QH_7") (pintype "passive"))
    )
    (net (code "85") (name "Net-(U4-IO0)") (class "Default")
      (node (ref "CJ3") (pin "2") (pintype "passive"))
      (node (ref "U4") (pin "13") (pinfunction "IO0_13") (pintype "passive"))
    )
    (net (code "86") (name "Net-(U4-IO1)") (class "Default")
      (node (ref "CJ4") (pin "2") (pintype "passive"))
      (node (ref "U4") (pin "14") (pinfunction "IO1_14") (pintype "passive"))
    )
    (net (code "87") (name "Net-(U4-IO2)") (class "Default")
      (node (ref "CJ5") (pin "2") (pintype "passive"))
      (node (ref "U4") (pin "15") (pinfunction "IO2_15") (pintype "passive"))
    )
    (net (code "88") (name "Net-(U4-IO3)") (class "Default")
      (node (ref "CJ2") (pin "2") (pintype "passive"))
      (node (ref "U4") (pin "12") (pinfunction "IO3_12") (pintype "passive"))
    )
    (net (code "89") (name "OUT") (class "Default")
      (node (ref "C5") (pin "1") (pinfunction "1_1") (pintype "passive"))
      (node (ref "PH5") (pin "1") (pinfunction "A_1") (pintype "passive"))
      (node (ref "PH5") (pin "4") (pinfunction "D_4") (pintype "passive"))
      (node (ref "R4") (pin "2") (pinfunction "2_2") (pintype "passive"))
      (node (ref "U5") (pin "3") (pinfunction "IO_3") (pintype "passive"))
    )
    (net (code "90") (name "VCC") (class "Default")
      (node (ref "89C52") (pin "31") (pinfunction "P4.6_31") (pintype "passive"))
      (node (ref "89C52") (pin "40") (pinfunction "VCC_40") (pintype "passive"))
      (node (ref "Bluetooth") (pin "5") (pinfunction "5_5") (pintype "passive"))
      (node (ref "C3") (pin "2") (pinfunction "2_2") (pintype "passive"))
      (node (ref "CJ1") (pin "1") (pintype "passive"))
      (node (ref "LCD1602") (pin "15") (pinfunction "A_15") (pintype "passive"))
      (node (ref "LCD1602") (pin "2") (pinfunction "VCC_2") (pintype "passive"))
      (node (ref "PR1") (pin "1") (pinfunction "*_1") (pintype "passive"))
      (node (ref "PR2") (pin "1") (pinfunction "*_1") (pintype "passive"))
      (node (ref "R0") (pin "2") (pinfunction "2_2") (pintype "passive"))
      (node (ref "R2") (pin "2") (pinfunction "2_2") (pintype "passive"))
      (node (ref "RP1") (pin "3") (pinfunction "3_3") (pintype "passive"))
      (node (ref "SW0") (pin "4") (pinfunction "4_4") (pintype "passive"))
      (node (ref "SW1") (pin "3") (pinfunction "3_3") (pintype "passive"))
      (node (ref "U1") (pin "20") (pinfunction "VCC_20") (pintype "passive"))
      (node (ref "U2") (pin "10") (pinfunction "SRCLR#_10") (pintype "passive"))
      (node (ref "U2") (pin "16") (pinfunction "VCC_16") (pintype "passive"))
      (node (ref "U3") (pin "1") (pinfunction "VDD_1") (pintype "passive"))
      (node (ref "U4") (pin "16") (pinfunction "VDD_16") (pintype "passive"))
      (node (ref "U5") (pin "16") (pinfunction "VDD_16") (pintype "passive"))
    )
    (net (code "91") (name "unconnected-(89C52-ALE{slash}P4.5-Pad30)") (class "Default")
      (node (ref "89C52") (pin "30") (pinfunction "ALE/P4.5_30") (pintype "passive"))
    )
    (net (code "92") (name "unconnected-(89C52-P4.4-Pad29)") (class "Default")
      (node (ref "89C52") (pin "29") (pinfunction "P4.4_29") (pintype "passive"))
    )
    (net (code "93") (name "unconnected-(PH1-B-Pad2)") (class "Default")
      (node (ref "PH1") (pin "2") (pinfunction "B_2") (pintype "passive"))
    )
    (net (code "94") (name "unconnected-(PH1-C-Pad3)") (class "Default")
      (node (ref "PH1") (pin "3") (pinfunction "C_3") (pintype "passive"))
    )
    (net (code "95") (name "unconnected-(PH2-B-Pad2)") (class "Default")
      (node (ref "PH2") (pin "2") (pinfunction "B_2") (pintype "passive"))
    )
    (net (code "96") (name "unconnected-(PH2-C-Pad3)") (class "Default")
      (node (ref "PH2") (pin "3") (pinfunction "C_3") (pintype "passive"))
    )
    (net (code "97") (name "unconnected-(PH3-B-Pad2)") (class "Default")
      (node (ref "PH3") (pin "2") (pinfunction "B_2") (pintype "passive"))
    )
    (net (code "98") (name "unconnected-(PH3-C-Pad3)") (class "Default")
      (node (ref "PH3") (pin "3") (pinfunction "C_3") (pintype "passive"))
    )
    (net (code "99") (name "unconnected-(PH4-B-Pad2)") (class "Default")
      (node (ref "PH4") (pin "2") (pinfunction "B_2") (pintype "passive"))
    )
    (net (code "100") (name "unconnected-(PH4-C-Pad3)") (class "Default")
      (node (ref "PH4") (pin "3") (pinfunction "C_3") (pintype "passive"))
    )
    (net (code "101") (name "unconnected-(PH5-B-Pad2)") (class "Default")
      (node (ref "PH5") (pin "2") (pinfunction "B_2") (pintype "passive"))
    )
    (net (code "102") (name "unconnected-(PH5-C-Pad3)") (class "Default")
      (node (ref "PH5") (pin "3") (pinfunction "C_3") (pintype "passive"))
    )
    (net (code "103") (name "unconnected-(SW0-Pad1)") (class "Default")
      (node (ref "SW0") (pin "1") (pinfunction "1_1") (pintype "passive"))
    )
    (net (code "104") (name "unconnected-(SW0-Pad2)") (class "Default")
      (node (ref "SW0") (pin "2") (pinfunction "2_2") (pintype "passive"))
    )
    (net (code "105") (name "unconnected-(SW0-Pad3)") (class "Default")
      (node (ref "SW0") (pin "3") (pinfunction "3_3") (pintype "passive"))
    )
    (net (code "106") (name "unconnected-(SW0-Pad6)") (class "Default")
      (node (ref "SW0") (pin "6") (pinfunction "6_6") (pintype "passive"))
    )
    (net (code "107") (name "unconnected-(SW1-Pad1)") (class "Default")
      (node (ref "SW1") (pin "1") (pinfunction "1_1") (pintype "passive"))
    )
    (net (code "108") (name "unconnected-(SW1-Pad2)") (class "Default")
      (node (ref "SW1") (pin "2") (pinfunction "2_2") (pintype "passive"))
    )
    (net (code "109") (name "unconnected-(U2-QH'-Pad9)") (class "Default")
      (node (ref "U2") (pin "9") (pinfunction "QH'_9") (pintype "passive"))
    )
    (net (code "110") (name "unconnected-(U4-IO4-Pad1)") (class "Default")
      (node (ref "U4") (pin "1") (pinfunction "IO4_1") (pintype "passive+no_connect"))
    )
    (net (code "111") (name "unconnected-(U4-IO5-Pad5)") (class "Default")
      (node (ref "U4") (pin "5") (pinfunction "IO5_5") (pintype "passive+no_connect"))
    )
    (net (code "112") (name "unconnected-(U4-IO6-Pad2)") (class "Default")
      (node (ref "U4") (pin "2") (pinfunction "IO6_2") (pintype "passive+no_connect"))
    )
    (net (code "113") (name "unconnected-(U4-IO7-Pad4)") (class "Default")
      (node (ref "U4") (pin "4") (pinfunction "IO7_4") (pintype "passive+no_connect"))
    )
  )
)
